# REV3.net
KiCad netlist of a schematic drawn in EAGLE
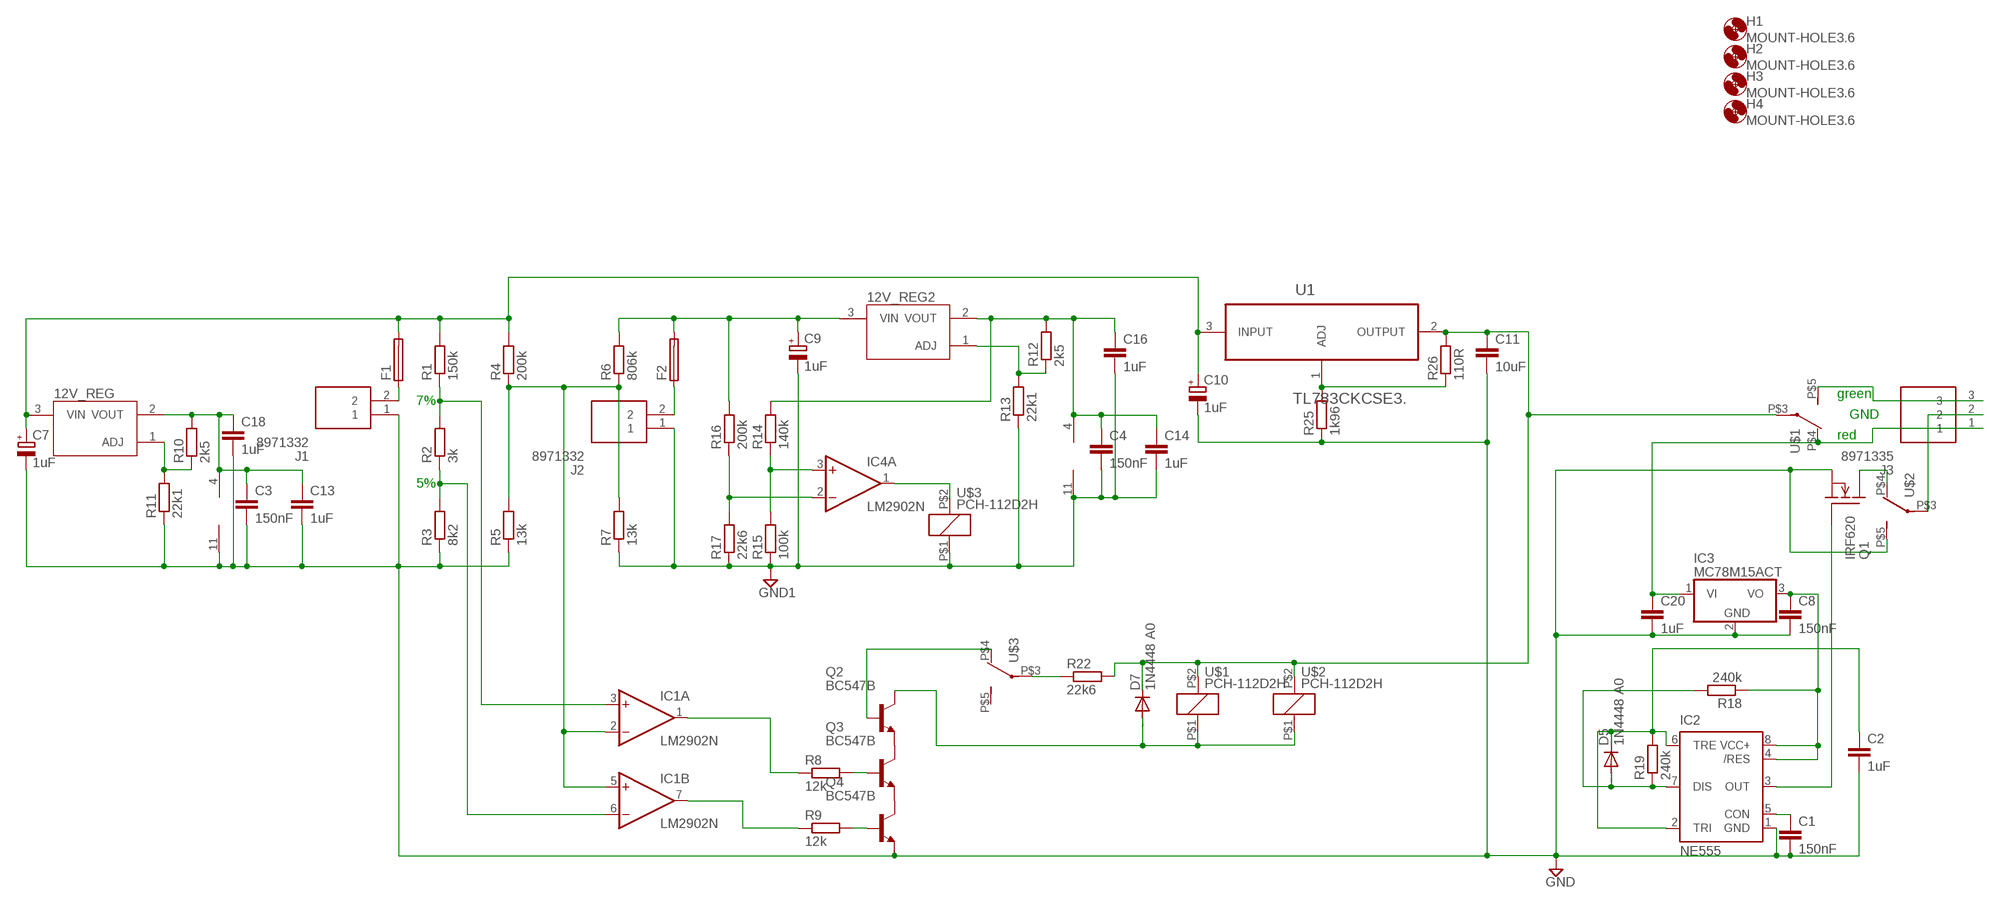
[diagram p0: schematic, sheet 1]

(export (version "E")
  (design (tool "Eeschema 10.0.6"))
  (components
    (comp (ref "12V_REG")
      (value "LR8LR8")
      (footprint "eagle-import:TO92-LINE")
      (libsource (lib "eagle-import") (part "LR8LR8"))
    )
    (comp (ref "12V_REG2")
      (value "LR8LR8")
      (footprint "eagle-import:TO92-LINE")
      (libsource (lib "eagle-import") (part "LR8LR8"))
    )
    (comp (ref "C1")
      (value "150nF")
      (footprint "eagle-import:C050-024X044")
      (libsource (lib "eagle-import") (part "C-EU050-024X044"))
    )
    (comp (ref "C2")
      (value "1uF")
      (footprint "eagle-import:C025-030X050")
      (libsource (lib "eagle-import") (part "C-EU025-030X050"))
    )
    (comp (ref "C3")
      (value "150nF")
      (footprint "eagle-import:C050-024X044")
      (libsource (lib "eagle-import") (part "C-EU050-024X044"))
    )
    (comp (ref "C4")
      (value "150nF")
      (footprint "eagle-import:C050-024X044")
      (libsource (lib "eagle-import") (part "C-EU050-024X044"))
    )
    (comp (ref "C7")
      (value "1uF")
      (footprint "eagle-import:E3,5-8")
      (libsource (lib "eagle-import") (part "CPOL-EUE3.5-8"))
    )
    (comp (ref "C8")
      (value "150nF")
      (footprint "eagle-import:C050-024X044")
      (libsource (lib "eagle-import") (part "C-EU050-024X044"))
    )
    (comp (ref "C9")
      (value "1uF")
      (footprint "eagle-import:E3,5-8")
      (libsource (lib "eagle-import") (part "CPOL-EUE3.5-8"))
    )
    (comp (ref "C10")
      (value "1uF")
      (footprint "eagle-import:E3,5-8")
      (libsource (lib "eagle-import") (part "CPOL-EUE3.5-8"))
    )
    (comp (ref "C11")
      (value "10uF")
      (footprint "eagle-import:C050-075X075")
      (libsource (lib "eagle-import") (part "C-EU050-075X075"))
    )
    (comp (ref "C13")
      (value "1uF")
      (footprint "eagle-import:C025-030X050")
      (libsource (lib "eagle-import") (part "C-EU025-030X050"))
    )
    (comp (ref "C14")
      (value "1uF")
      (footprint "eagle-import:C025-030X050")
      (libsource (lib "eagle-import") (part "C-EU025-030X050"))
    )
    (comp (ref "C16")
      (value "1uF")
      (footprint "eagle-import:C025-030X050")
      (libsource (lib "eagle-import") (part "C-EU025-030X050"))
    )
    (comp (ref "C18")
      (value "1uF")
      (footprint "eagle-import:C025-030X050")
      (libsource (lib "eagle-import") (part "C-EU025-030X050"))
    )
    (comp (ref "C20")
      (value "1uF")
      (footprint "eagle-import:C025-030X050")
      (libsource (lib "eagle-import") (part "C-EU025-030X050"))
    )
    (comp (ref "D5")
      (value "1N4448 A0")
      (footprint "eagle-import:DO35-10")
      (libsource (lib "eagle-import") (part "1N4446"))
    )
    (comp (ref "D7")
      (value "1N4448 A0")
      (footprint "eagle-import:DO35-10")
      (libsource (lib "eagle-import") (part "1N4446"))
    )
    (comp (ref "F1")
      (value "GSH15")
      (footprint "eagle-import:GSH15")
      (fields (field (name "MPN") "64900001039"))
      (libsource (lib "eagle-import") (part "GSH15"))
    )
    (comp (ref "F2")
      (value "GSH15")
      (footprint "eagle-import:GSH15")
      (fields (field (name "MPN") "64900001039"))
      (libsource (lib "eagle-import") (part "GSH15"))
    )
    (comp (ref "H1")
      (value "MOUNT-HOLE3.6")
      (footprint "eagle-import:3,6")
      (libsource (lib "eagle-import") (part "MOUNT-HOLE3.6"))
    )
    (comp (ref "H2")
      (value "MOUNT-HOLE3.6")
      (footprint "eagle-import:3,6")
      (libsource (lib "eagle-import") (part "MOUNT-HOLE3.6"))
    )
    (comp (ref "H3")
      (value "MOUNT-HOLE3.6")
      (footprint "eagle-import:3,6")
      (libsource (lib "eagle-import") (part "MOUNT-HOLE3.6"))
    )
    (comp (ref "H4")
      (value "MOUNT-HOLE3.6")
      (footprint "eagle-import:3,6")
      (libsource (lib "eagle-import") (part "MOUNT-HOLE3.6"))
    )
    (comp (ref "IC1")
      (value "LM2902N")
      (footprint "eagle-import:DIL14")
      (libsource (lib "eagle-import") (part "LM2902N"))
    )
    (comp (ref "IC2")
      (value "NE555")
      (footprint "eagle-import:DIL-08")
      (fields (field (name "MF") "Arrow Electronics") (field (name "MPN") "NE555N"))
      (libsource (lib "eagle-import") (part "NE555"))
    )
    (comp (ref "IC3")
      (value "MC78M15ACT")
      (footprint "eagle-import:TO220V")
      (libsource (lib "eagle-import") (part "MC78MT15AC"))
    )
    (comp (ref "IC4")
      (value "LM2902N")
      (footprint "eagle-import:DIL14")
      (libsource (lib "eagle-import") (part "LM2902N"))
    )
    (comp (ref "J1")
      (value "8971332")
      (footprint "eagle-import:SHDR2W90P0X350_1X2_700X700X850")
      (libsource (lib "eagle-import") (part "8971332"))
    )
    (comp (ref "J2")
      (value "8971332")
      (footprint "eagle-import:SHDR2W90P0X350_1X2_700X700X850")
      (libsource (lib "eagle-import") (part "8971332"))
    )
    (comp (ref "J3")
      (value "8971335")
      (footprint "eagle-import:SHDR3W90P0X350_1X3_1050X700X85")
      (libsource (lib "eagle-import") (part "8971335"))
    )
    (comp (ref "Q1")
      (value "IRF620")
      (footprint "eagle-import:TO220")
      (libsource (lib "eagle-import") (part "IRF620"))
    )
    (comp (ref "Q2")
      (value "BC547B")
      (footprint "eagle-import:TO92")
      (libsource (lib "eagle-import") (part "BC547B"))
    )
    (comp (ref "Q3")
      (value "BC547B")
      (footprint "eagle-import:TO92")
      (libsource (lib "eagle-import") (part "BC547B"))
    )
    (comp (ref "Q4")
      (value "BC547B")
      (footprint "eagle-import:TO92")
      (libsource (lib "eagle-import") (part "BC547B"))
    )
    (comp (ref "R1")
      (value "150k")
      (footprint "eagle-import:0207_10")
      (libsource (lib "eagle-import") (part "R-EU_0207/10"))
    )
    (comp (ref "R2")
      (value "3k")
      (footprint "eagle-import:0207_10")
      (libsource (lib "eagle-import") (part "R-EU_0207/10"))
    )
    (comp (ref "R3")
      (value "8k2")
      (footprint "eagle-import:0207_10")
      (libsource (lib "eagle-import") (part "R-EU_0207/10"))
    )
    (comp (ref "R4")
      (value "200k")
      (footprint "eagle-import:0207_10")
      (libsource (lib "eagle-import") (part "R-EU_0207/10"))
    )
    (comp (ref "R5")
      (value "13k")
      (footprint "eagle-import:0207_10")
      (libsource (lib "eagle-import") (part "R-EU_0207/10"))
    )
    (comp (ref "R6")
      (value "806k")
      (footprint "eagle-import:0207_10")
      (libsource (lib "eagle-import") (part "R-EU_0207/10"))
    )
    (comp (ref "R7")
      (value "13k")
      (footprint "eagle-import:0207_10")
      (libsource (lib "eagle-import") (part "R-EU_0207/10"))
    )
    (comp (ref "R8")
      (value "12k")
      (footprint "eagle-import:0207_10")
      (libsource (lib "eagle-import") (part "R-EU_0207/10"))
    )
    (comp (ref "R9")
      (value "12k")
      (footprint "eagle-import:0207_10")
      (libsource (lib "eagle-import") (part "R-EU_0207/10"))
    )
    (comp (ref "R10")
      (value "2k5")
      (footprint "eagle-import:0207_10")
      (libsource (lib "eagle-import") (part "R-EU_0207/10"))
    )
    (comp (ref "R11")
      (value "22k1")
      (footprint "eagle-import:0207_10")
      (libsource (lib "eagle-import") (part "R-EU_0207/10"))
    )
    (comp (ref "R12")
      (value "2k5")
      (footprint "eagle-import:0207_10")
      (libsource (lib "eagle-import") (part "R-EU_0207/10"))
    )
    (comp (ref "R13")
      (value "22k1")
      (footprint "eagle-import:0207_10")
      (libsource (lib "eagle-import") (part "R-EU_0207/10"))
    )
    (comp (ref "R14")
      (value "140k")
      (footprint "eagle-import:0207_10")
      (libsource (lib "eagle-import") (part "R-EU_0207/10"))
    )
    (comp (ref "R15")
      (value "100k")
      (footprint "eagle-import:0207_10")
      (libsource (lib "eagle-import") (part "R-EU_0207/10"))
    )
    (comp (ref "R16")
      (value "200k")
      (footprint "eagle-import:0207_10")
      (libsource (lib "eagle-import") (part "R-EU_0207/10"))
    )
    (comp (ref "R17")
      (value "22k6")
      (footprint "eagle-import:0207_10")
      (libsource (lib "eagle-import") (part "R-EU_0207/10"))
    )
    (comp (ref "R18")
      (value "240k")
      (footprint "eagle-import:0207_10")
      (libsource (lib "eagle-import") (part "R-EU_0207/10"))
    )
    (comp (ref "R19")
      (value "240k")
      (footprint "eagle-import:0207_10")
      (libsource (lib "eagle-import") (part "R-EU_0207/10"))
    )
    (comp (ref "R22")
      (value "22k6")
      (footprint "eagle-import:0207_10")
      (libsource (lib "eagle-import") (part "R-EU_0207/10"))
    )
    (comp (ref "R25")
      (value "1k96")
      (footprint "eagle-import:0309_10")
      (libsource (lib "eagle-import") (part "R-EU_0309/10"))
    )
    (comp (ref "R26")
      (value "110R")
      (footprint "eagle-import:0309_10")
      (libsource (lib "eagle-import") (part "R-EU_0309/10"))
    )
    (comp (ref "U$1")
      (value "PCH-112D2H")
      (footprint "eagle-import:PCH-112D2H")
      (libsource (lib "eagle-import") (part "PCH-112D2H"))
    )
    (comp (ref "U$2")
      (value "PCH-112D2H")
      (footprint "eagle-import:PCH-112D2H")
      (libsource (lib "eagle-import") (part "PCH-112D2H"))
    )
    (comp (ref "U$3")
      (value "PCH-112D2H")
      (footprint "eagle-import:PCH-112D2H")
      (libsource (lib "eagle-import") (part "PCH-112D2H"))
    )
    (comp (ref "U1")
      (value "TL783CKCSE3.")
      (footprint "eagle-import:TO254P457X1016X2222-3P")
      (libsource (lib "eagle-import") (part "TL783CKCSE3."))
    )
  )
  (nets
    (net (code "1") (name "GND") (class "Default")
      (node (ref "C1") (pin "2") (pinfunction "2_2") (pintype "passive"))
      (node (ref "C10") (pin "-") (pinfunction "-_-") (pintype "passive"))
      (node (ref "C11") (pin "2") (pinfunction "2_2") (pintype "passive"))
      (node (ref "C13") (pin "2") (pinfunction "2_2") (pintype "passive"))
      (node (ref "C18") (pin "2") (pinfunction "2_2") (pintype "passive"))
      (node (ref "C2") (pin "2") (pinfunction "2_2") (pintype "passive"))
      (node (ref "C20") (pin "2") (pinfunction "2_2") (pintype "passive"))
      (node (ref "C3") (pin "2") (pinfunction "2_2") (pintype "passive"))
      (node (ref "C7") (pin "-") (pinfunction "-_-") (pintype "passive"))
      (node (ref "C8") (pin "2") (pinfunction "2_2") (pintype "passive"))
      (node (ref "IC1") (pin "11") (pinfunction "V-_11") (pintype "power_in"))
      (node (ref "IC2") (pin "1") (pinfunction "GND_1") (pintype "power_in"))
      (node (ref "IC3") (pin "2") (pinfunction "GND_2") (pintype "passive"))
      (node (ref "J1") (pin "1") (pinfunction "1_1") (pintype "bidirectional"))
      (node (ref "Q1") (pin "3") (pinfunction "S_3") (pintype "passive"))
      (node (ref "Q4") (pin "1") (pinfunction "E_1") (pintype "passive"))
      (node (ref "R11") (pin "1") (pinfunction "1_1") (pintype "passive"))
      (node (ref "R25") (pin "1") (pinfunction "1_1") (pintype "passive"))
      (node (ref "R3") (pin "1") (pinfunction "1_1") (pintype "passive"))
      (node (ref "R5") (pin "1") (pinfunction "1_1") (pintype "passive"))
      (node (ref "U$2") (pin "P$5") (pinfunction "S_P$5") (pintype "passive"))
    )
    (net (code "2") (name "GND1") (class "Default")
      (node (ref "C14") (pin "2") (pinfunction "2_2") (pintype "passive"))
      (node (ref "C16") (pin "2") (pinfunction "2_2") (pintype "passive"))
      (node (ref "C4") (pin "2") (pinfunction "2_2") (pintype "passive"))
      (node (ref "C9") (pin "-") (pinfunction "-_-") (pintype "passive"))
      (node (ref "IC4") (pin "11") (pinfunction "V-_11") (pintype "power_in"))
      (node (ref "J2") (pin "1") (pinfunction "1_1") (pintype "bidirectional"))
      (node (ref "R13") (pin "1") (pinfunction "1_1") (pintype "passive"))
      (node (ref "R15") (pin "1") (pinfunction "1_1") (pintype "passive"))
      (node (ref "R17") (pin "1") (pinfunction "1_1") (pintype "passive"))
      (node (ref "R7") (pin "1") (pinfunction "1_1") (pintype "passive"))
      (node (ref "U$3") (pin "P$1") (pinfunction "2_P$1") (pintype "passive"))
    )
    (net (code "3") (name "Net-(12V_REG-ADJ)") (class "Default")
      (node (ref "12V_REG") (pin "1") (pinfunction "ADJ_1") (pintype "bidirectional"))
      (node (ref "R10") (pin "1") (pinfunction "1_1") (pintype "passive"))
      (node (ref "R11") (pin "2") (pinfunction "2_2") (pintype "passive"))
    )
    (net (code "4") (name "Net-(12V_REG-VIN)") (class "Default")
      (node (ref "12V_REG") (pin "3") (pinfunction "VIN_3") (pintype "bidirectional"))
      (node (ref "C10") (pin "+") (pinfunction "+_+") (pintype "passive"))
      (node (ref "C7") (pin "+") (pinfunction "+_+") (pintype "passive"))
      (node (ref "F1") (pin "2") (pinfunction "2_2") (pintype "passive"))
      (node (ref "R1") (pin "2") (pinfunction "2_2") (pintype "passive"))
      (node (ref "R4") (pin "2") (pinfunction "2_2") (pintype "passive"))
      (node (ref "U1") (pin "3") (pinfunction "INPUT_3") (pintype "input"))
    )
    (net (code "5") (name "Net-(12V_REG-VOUT)") (class "Default")
      (node (ref "12V_REG") (pin "2") (pinfunction "VOUT_2") (pintype "bidirectional"))
      (node (ref "C13") (pin "1") (pinfunction "1_1") (pintype "passive"))
      (node (ref "C18") (pin "1") (pinfunction "1_1") (pintype "passive"))
      (node (ref "C3") (pin "1") (pinfunction "1_1") (pintype "passive"))
      (node (ref "IC1") (pin "4") (pinfunction "V+_4") (pintype "power_in"))
      (node (ref "R10") (pin "2") (pinfunction "2_2") (pintype "passive"))
    )
    (net (code "6") (name "Net-(12V_REG2-ADJ)") (class "Default")
      (node (ref "12V_REG2") (pin "1") (pinfunction "ADJ_1") (pintype "bidirectional"))
      (node (ref "R12") (pin "1") (pinfunction "1_1") (pintype "passive"))
      (node (ref "R13") (pin "2") (pinfunction "2_2") (pintype "passive"))
    )
    (net (code "7") (name "Net-(12V_REG2-VIN)") (class "Default")
      (node (ref "12V_REG2") (pin "3") (pinfunction "VIN_3") (pintype "bidirectional"))
      (node (ref "C9") (pin "+") (pinfunction "+_+") (pintype "passive"))
      (node (ref "F2") (pin "2") (pinfunction "2_2") (pintype "passive"))
      (node (ref "R16") (pin "2") (pinfunction "2_2") (pintype "passive"))
      (node (ref "R6") (pin "2") (pinfunction "2_2") (pintype "passive"))
    )
    (net (code "8") (name "Net-(12V_REG2-VOUT)") (class "Default")
      (node (ref "12V_REG2") (pin "2") (pinfunction "VOUT_2") (pintype "bidirectional"))
      (node (ref "C14") (pin "1") (pinfunction "1_1") (pintype "passive"))
      (node (ref "C16") (pin "1") (pinfunction "1_1") (pintype "passive"))
      (node (ref "C4") (pin "1") (pinfunction "1_1") (pintype "passive"))
      (node (ref "IC4") (pin "4") (pinfunction "V+_4") (pintype "power_in"))
      (node (ref "R12") (pin "2") (pinfunction "2_2") (pintype "passive"))
      (node (ref "R14") (pin "2") (pinfunction "2_2") (pintype "passive"))
    )
    (net (code "9") (name "Net-(F1-Pad1)") (class "Default")
      (node (ref "F1") (pin "1") (pinfunction "1_1") (pintype "passive"))
      (node (ref "J1") (pin "2") (pinfunction "2_2") (pintype "bidirectional"))
    )
    (net (code "10") (name "Net-(F2-Pad1)") (class "Default")
      (node (ref "F2") (pin "1") (pinfunction "1_1") (pintype "passive"))
      (node (ref "J2") (pin "2") (pinfunction "2_2") (pintype "bidirectional"))
    )
    (net (code "11") (name "Net-(IC1A-+IN)") (class "Default")
      (node (ref "IC1") (pin "3") (pinfunction "+IN_3") (pintype "input"))
      (node (ref "R1") (pin "1") (pinfunction "1_1") (pintype "passive"))
      (node (ref "R2") (pin "2") (pinfunction "2_2") (pintype "passive"))
    )
    (net (code "12") (name "Net-(IC1A--IN)") (class "Default")
      (node (ref "IC1") (pin "2") (pinfunction "-IN_2") (pintype "input"))
      (node (ref "IC1") (pin "5") (pinfunction "+IN_5") (pintype "input"))
      (node (ref "R4") (pin "1") (pinfunction "1_1") (pintype "passive"))
      (node (ref "R5") (pin "2") (pinfunction "2_2") (pintype "passive"))
      (node (ref "R6") (pin "1") (pinfunction "1_1") (pintype "passive"))
      (node (ref "R7") (pin "2") (pinfunction "2_2") (pintype "passive"))
    )
    (net (code "13") (name "Net-(IC1A-OUT)") (class "Default")
      (node (ref "IC1") (pin "1") (pinfunction "OUT_1") (pintype "output"))
      (node (ref "R8") (pin "1") (pinfunction "1_1") (pintype "passive"))
    )
    (net (code "14") (name "Net-(IC1B--IN)") (class "Default")
      (node (ref "IC1") (pin "6") (pinfunction "-IN_6") (pintype "input"))
      (node (ref "R2") (pin "1") (pinfunction "1_1") (pintype "passive"))
      (node (ref "R3") (pin "2") (pinfunction "2_2") (pintype "passive"))
    )
    (net (code "15") (name "Net-(IC1B-OUT)") (class "Default")
      (node (ref "IC1") (pin "7") (pinfunction "OUT_7") (pintype "output"))
      (node (ref "R9") (pin "1") (pinfunction "1_1") (pintype "passive"))
    )
    (net (code "16") (name "Net-(IC2-CON)") (class "Default")
      (node (ref "C1") (pin "1") (pinfunction "1_1") (pintype "passive"))
      (node (ref "IC2") (pin "5") (pinfunction "CON_5") (pintype "input"))
    )
    (net (code "17") (name "Net-(IC2-DIS)") (class "Default")
      (node (ref "D5") (pin "A") (pinfunction "A_A") (pintype "passive"))
      (node (ref "IC2") (pin "7") (pinfunction "DIS_7") (pintype "input"))
      (node (ref "R18") (pin "2") (pinfunction "2_2") (pintype "passive"))
      (node (ref "R19") (pin "1") (pinfunction "1_1") (pintype "passive"))
    )
    (net (code "18") (name "Net-(IC2-OUT)") (class "Default")
      (node (ref "IC2") (pin "3") (pinfunction "OUT_3") (pintype "output"))
      (node (ref "Q1") (pin "1") (pinfunction "G_1") (pintype "passive"))
    )
    (net (code "19") (name "Net-(IC2-TRE)") (class "Default")
      (node (ref "C2") (pin "1") (pinfunction "1_1") (pintype "passive"))
      (node (ref "D5") (pin "C") (pinfunction "C_C") (pintype "passive"))
      (node (ref "IC2") (pin "2") (pinfunction "TRI_2") (pintype "input"))
      (node (ref "IC2") (pin "6") (pinfunction "TRE_6") (pintype "input"))
      (node (ref "R19") (pin "2") (pinfunction "2_2") (pintype "passive"))
    )
    (net (code "20") (name "Net-(IC2-VCC+)") (class "Default")
      (node (ref "C8") (pin "1") (pinfunction "1_1") (pintype "passive"))
      (node (ref "IC2") (pin "4") (pinfunction "/RES_4") (pintype "input"))
      (node (ref "IC2") (pin "8") (pinfunction "VCC+_8") (pintype "power_in"))
      (node (ref "IC3") (pin "3") (pinfunction "VO_3") (pintype "passive"))
      (node (ref "R18") (pin "1") (pinfunction "1_1") (pintype "passive"))
    )
    (net (code "21") (name "Net-(IC3-VI)") (class "Default")
      (node (ref "C20") (pin "1") (pinfunction "1_1") (pintype "passive"))
      (node (ref "IC3") (pin "1") (pinfunction "VI_1") (pintype "input"))
      (node (ref "J3") (pin "1") (pinfunction "1_1") (pintype "bidirectional"))
      (node (ref "U$1") (pin "P$4") (pinfunction "O_P$4") (pintype "passive"))
    )
    (net (code "22") (name "Net-(IC4A-+IN)") (class "Default")
      (node (ref "IC4") (pin "3") (pinfunction "+IN_3") (pintype "input"))
      (node (ref "R14") (pin "1") (pinfunction "1_1") (pintype "passive"))
      (node (ref "R15") (pin "2") (pinfunction "2_2") (pintype "passive"))
    )
    (net (code "23") (name "Net-(IC4A--IN)") (class "Default")
      (node (ref "IC4") (pin "2") (pinfunction "-IN_2") (pintype "input"))
      (node (ref "R16") (pin "1") (pinfunction "1_1") (pintype "passive"))
      (node (ref "R17") (pin "2") (pinfunction "2_2") (pintype "passive"))
    )
    (net (code "24") (name "Net-(IC4A-OUT)") (class "Default")
      (node (ref "IC4") (pin "1") (pinfunction "OUT_1") (pintype "output"))
      (node (ref "U$3") (pin "P$2") (pinfunction "1_P$2") (pintype "passive"))
    )
    (net (code "25") (name "Net-(Q1-D)") (class "Default")
      (node (ref "Q1") (pin "2") (pinfunction "D_2") (pintype "passive"))
      (node (ref "U$2") (pin "P$4") (pinfunction "O_P$4") (pintype "passive"))
    )
    (net (code "26") (name "Net-(Q2-B)") (class "Default")
      (node (ref "Q2") (pin "2") (pinfunction "B_2") (pintype "passive"))
      (node (ref "U$3") (pin "P$4") (pinfunction "O_P$4") (pintype "passive"))
    )
    (net (code "27") (name "Net-(Q2-C)") (class "Default")
      (node (ref "D7") (pin "A") (pinfunction "A_A") (pintype "passive"))
      (node (ref "Q2") (pin "3") (pinfunction "C_3") (pintype "passive"))
      (node (ref "U$1") (pin "P$1") (pinfunction "2_P$1") (pintype "passive"))
      (node (ref "U$2") (pin "P$1") (pinfunction "2_P$1") (pintype "passive"))
    )
    (net (code "28") (name "Net-(Q2-E)") (class "Default")
      (node (ref "Q2") (pin "1") (pinfunction "E_1") (pintype "passive"))
      (node (ref "Q3") (pin "3") (pinfunction "C_3") (pintype "passive"))
    )
    (net (code "29") (name "Net-(Q3-B)") (class "Default")
      (node (ref "Q3") (pin "2") (pinfunction "B_2") (pintype "passive"))
      (node (ref "R8") (pin "2") (pinfunction "2_2") (pintype "passive"))
    )
    (net (code "30") (name "Net-(Q3-E)") (class "Default")
      (node (ref "Q3") (pin "1") (pinfunction "E_1") (pintype "passive"))
      (node (ref "Q4") (pin "3") (pinfunction "C_3") (pintype "passive"))
    )
    (net (code "31") (name "Net-(Q4-B)") (class "Default")
      (node (ref "Q4") (pin "2") (pinfunction "B_2") (pintype "passive"))
      (node (ref "R9") (pin "2") (pinfunction "2_2") (pintype "passive"))
    )
    (net (code "32") (name "Net-(U$1A-1)") (class "Default")
      (node (ref "C11") (pin "1") (pinfunction "1_1") (pintype "passive"))
      (node (ref "D7") (pin "C") (pinfunction "C_C") (pintype "passive"))
      (node (ref "R22") (pin "2") (pinfunction "2_2") (pintype "passive"))
      (node (ref "R26") (pin "2") (pinfunction "2_2") (pintype "passive"))
      (node (ref "U$1") (pin "P$2") (pinfunction "1_P$2") (pintype "passive"))
      (node (ref "U$1") (pin "P$3") (pinfunction "P_P$3") (pintype "passive"))
      (node (ref "U$2") (pin "P$2") (pinfunction "1_P$2") (pintype "passive"))
      (node (ref "U1") (pin "2") (pinfunction "OUTPUT_2") (pintype "output"))
    )
    (net (code "33") (name "Net-(U$1B-S)") (class "Default")
      (node (ref "J3") (pin "3") (pinfunction "3_3") (pintype "bidirectional"))
      (node (ref "U$1") (pin "P$5") (pinfunction "S_P$5") (pintype "passive"))
    )
    (net (code "34") (name "Net-(U$2B-P)") (class "Default")
      (node (ref "J3") (pin "2") (pinfunction "2_2") (pintype "bidirectional"))
      (node (ref "U$2") (pin "P$3") (pinfunction "P_P$3") (pintype "passive"))
    )
    (net (code "35") (name "Net-(U$3B-P)") (class "Default")
      (node (ref "R22") (pin "1") (pinfunction "1_1") (pintype "passive"))
      (node (ref "U$3") (pin "P$3") (pinfunction "P_P$3") (pintype "passive"))
    )
    (net (code "36") (name "Net-(U1-ADJ)") (class "Default")
      (node (ref "R25") (pin "2") (pinfunction "2_2") (pintype "passive"))
      (node (ref "R26") (pin "1") (pinfunction "1_1") (pintype "passive"))
      (node (ref "U1") (pin "1") (pinfunction "ADJ_1") (pintype "passive"))
    )
    (net (code "37") (name "unconnected-(U$3B-S-PadP$5)") (class "Default")
      (node (ref "U$3") (pin "P$5") (pinfunction "S_P$5") (pintype "passive"))
    )
  )
)
